# ADC.net
KiCad netlist of a schematic drawn in Altium Designer
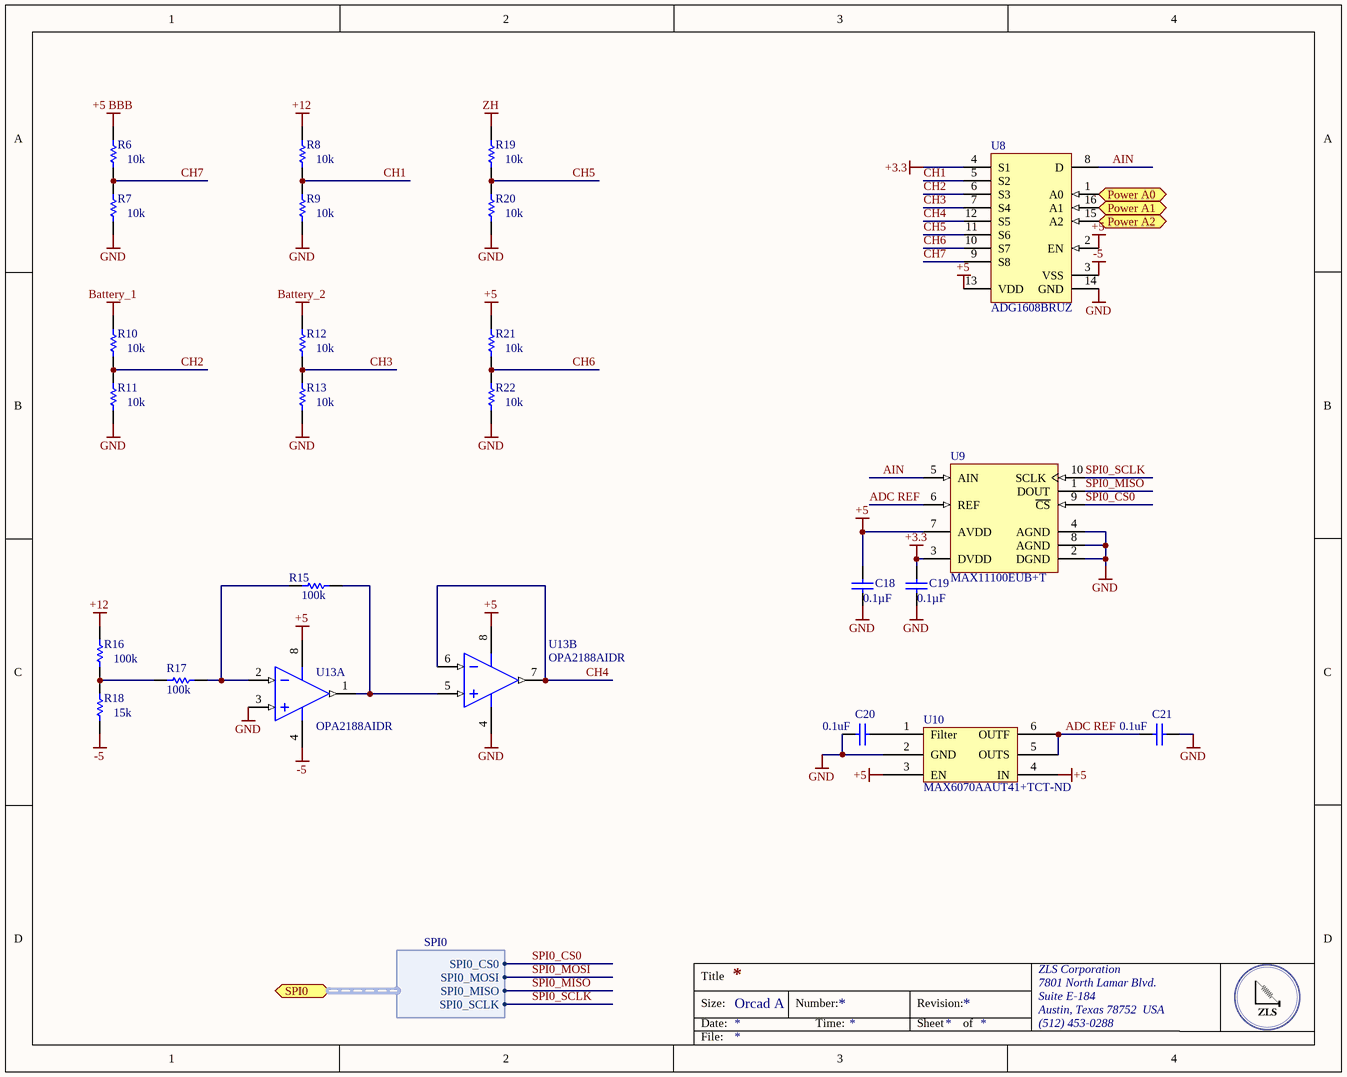
[diagram p0: ADC.SchDoc]

(export (version "E")
  (design (tool "Eeschema 10.0.6"))
  (components
    (comp (ref "C18")
      (value "CAP CER 0.1UF 25V X7R 0805")
      (footprint "CAPC0805(2012)145_N")
      (fields
        (field (name "MANUFACTURER") "Murata Electronics North America")
        (field (name "MANUFACTURER PART NUMBER") "GRM21BR71E104KA01L")
        (field (name "CAPACITANCE") "0.1µF")
        (field (name "TOLERANCE") "±10%")
      )
      (libsource (lib "Altium Content Vault") (part "CMP-1036-04795-1"))
    )
    (comp (ref "C19")
      (value "CAP CER 0.1UF 25V X7R 0805")
      (footprint "CAPC0805(2012)145_N")
      (fields
        (field (name "MANUFACTURER") "Murata Electronics North America")
        (field (name "MANUFACTURER PART NUMBER") "GRM21BR71E104KA01L")
        (field (name "CAPACITANCE") "0.1µF")
        (field (name "TOLERANCE") "±10%")
      )
      (libsource (lib "Altium Content Vault") (part "CMP-1036-04795-1"))
    )
    (comp (ref "C20")
      (value "0.1uF")
      (footprint "CAPC0402(1005)60_L")
      (description "CAP CER 0.1UF 10V X7R 0402")
      (fields
        (field (name "MANUFACTURER") "Murata Electronics North America")
        (field (name "MANUFACTURER PART NUMBER") "GRM155R71A104KA01D")
      )
      (libsource (lib "Altium Content Vault") (part "CMP-1034-00252-1"))
    )
    (comp (ref "C21")
      (value "0.1uF")
      (footprint "CAPC0402(1005)60_L")
      (description "CAP CER 0.1UF 10V X7R 0402")
      (fields
        (field (name "MANUFACTURER") "Murata Electronics North America")
        (field (name "MANUFACTURER PART NUMBER") "GRM155R71A104KA01D")
      )
      (libsource (lib "Altium Content Vault") (part "CMP-1034-00252-1"))
    )
    (comp (ref "R6")
      (value "10k")
      (footprint "RESC0402(1005)_L")
      (libsource (lib "Altium Content Vault") (part "CMP-1011-00927-1"))
    )
    (comp (ref "R7")
      (value "10k")
      (footprint "RESC0402(1005)_L")
      (libsource (lib "Altium Content Vault") (part "CMP-1011-00927-1"))
    )
    (comp (ref "R8")
      (value "10k")
      (footprint "RESC0402(1005)_L")
      (libsource (lib "Altium Content Vault") (part "CMP-1011-00927-1"))
    )
    (comp (ref "R9")
      (value "10k")
      (footprint "RESC0402(1005)_L")
      (libsource (lib "Altium Content Vault") (part "CMP-1011-00927-1"))
    )
    (comp (ref "R10")
      (value "10k")
      (footprint "RESC0402(1005)_L")
      (libsource (lib "Altium Content Vault") (part "CMP-1011-00927-1"))
    )
    (comp (ref "R11")
      (value "10k")
      (footprint "RESC0402(1005)_L")
      (libsource (lib "Altium Content Vault") (part "CMP-1011-00927-1"))
    )
    (comp (ref "R12")
      (value "10k")
      (footprint "RESC0402(1005)_L")
      (libsource (lib "Altium Content Vault") (part "CMP-1011-00927-1"))
    )
    (comp (ref "R13")
      (value "10k")
      (footprint "RESC0402(1005)_L")
      (libsource (lib "Altium Content Vault") (part "CMP-1011-00927-1"))
    )
    (comp (ref "R15")
      (value "100k")
      (footprint "RESC0402(1005)_L")
      (libsource (lib "Altium Content Vault") (part "CMP-1011-00927-1"))
    )
    (comp (ref "R16")
      (value "100k")
      (footprint "RESC0402(1005)_L")
      (libsource (lib "Altium Content Vault") (part "CMP-1011-00927-1"))
    )
    (comp (ref "R17")
      (value "100k")
      (footprint "RESC0402(1005)_L")
      (libsource (lib "Altium Content Vault") (part "CMP-1011-00927-1"))
    )
    (comp (ref "R18")
      (value "15k")
      (footprint "RESC0402(1005)_L")
      (libsource (lib "Altium Content Vault") (part "CMP-1011-00927-1"))
    )
    (comp (ref "R19")
      (value "10k")
      (footprint "RESC0402(1005)_L")
      (libsource (lib "Altium Content Vault") (part "CMP-1011-00927-1"))
    )
    (comp (ref "R20")
      (value "10k")
      (footprint "RESC0402(1005)_L")
      (libsource (lib "Altium Content Vault") (part "CMP-1011-00927-1"))
    )
    (comp (ref "R21")
      (value "10k")
      (footprint "RESC0402(1005)_L")
      (libsource (lib "Altium Content Vault") (part "CMP-1011-00927-1"))
    )
    (comp (ref "R22")
      (value "10k")
      (footprint "RESC0402(1005)_L")
      (libsource (lib "Altium Content Vault") (part "CMP-1011-00927-1"))
    )
    (comp (ref "U8")
      (value "ADG1608BRUZ")
      (footprint "ADI-RU-16_M")
      (description "4.5 Ohm Ron, 8-Channel +/-5 V,+12 V, +5 V and +3.3 V Multiplexer, 16-pin SOP (RU-16), Tube")
      (fields (field (name "MANUFACTURER") "Analog Devices"))
      (libsource (lib "Altium Content Vault") (part "ADI-ADG1608-RU-16"))
    )
    (comp (ref "U9")
      (value "MAX11100EUB+T")
      (footprint "U10+2_L")
      (description "16-Bit, +5V, 200ksps ADC with 10uA Shutdown, 10-Pin uMAX, -40°C to +85°C, Pb-Free, Tape and Reel")
      (libsource (lib "Altium Content Vault") (part "CON-ADC-MAX11100-IL10"))
    )
    (comp (ref "U10")
      (value "MAX6070AAUT41+T")
      (footprint "SOT95P280X445-6N")
      (description "IC VREF SERIES 4.096V SOT23")
      (fields
        (field (name "SUPPLIER PART NUMBER 1") "MAX6070AAUT41+TCT-ND")
        (field (name "MANUFACTURER") "Maxim Integrated")
        (field (name "TOLERANCE") "±0.04%")
      )
      (libsource (lib "ZLS_Schematic_lib") (part "MAX6070AAUT41+T"))
    )
    (comp (ref "U13")
      (value "OPA2188AIDR")
      (footprint "D0008A_L")
      (fields (field (name "MANUFACTURER") "Texas Instruments"))
      (libsource (lib "Altium Content Vault") (part "TI-OPA-8_2"))
    )
  )
  (nets
    (net (code "2") (name "+3.3") (class "Default")
      (node (ref "C19") (pin "1") (pinfunction "1_1") (pintype "passive"))
      (node (ref "U8") (pin "4") (pinfunction "S1_4") (pintype "passive"))
      (node (ref "U9") (pin "3") (pinfunction "DVDD_3") (pintype "power_in"))
    )
    (net (code "3") (name "+5") (class "Default")
      (node (ref "C18") (pin "1") (pinfunction "1_1") (pintype "passive"))
      (node (ref "R21") (pin "2") (pinfunction "2_2") (pintype "passive"))
      (node (ref "U10") (pin "3") (pinfunction "EN_3") (pintype "passive"))
      (node (ref "U10") (pin "4") (pinfunction "IN_4") (pintype "passive"))
      (node (ref "U13") (pin "8") (pinfunction "V+_8") (pintype "power_in"))
      (node (ref "U8") (pin "13") (pinfunction "VDD_13") (pintype "power_in"))
      (node (ref "U8") (pin "2") (pinfunction "EN_2") (pintype "input"))
      (node (ref "U9") (pin "7") (pinfunction "AVDD_7") (pintype "power_in"))
    )
    (net (code "4") (name "+5 BBB") (class "Default")
      (node (ref "R6") (pin "2") (pinfunction "2_2") (pintype "passive"))
    )
    (net (code "5") (name "+12") (class "Default")
      (node (ref "R16") (pin "2") (pinfunction "2_2") (pintype "passive"))
      (node (ref "R8") (pin "2") (pinfunction "2_2") (pintype "passive"))
    )
    (net (code "6") (name "-5") (class "Default")
      (node (ref "R18") (pin "1") (pinfunction "1_1") (pintype "passive"))
      (node (ref "U13") (pin "4") (pinfunction "V-_4") (pintype "power_in"))
      (node (ref "U8") (pin "3") (pinfunction "VSS_3") (pintype "power_in"))
    )
    (net (code "7") (name "/ADC REF") (class "Default")
      (node (ref "C21") (pin "2") (pinfunction "2_2") (pintype "passive"))
      (node (ref "U10") (pin "5") (pinfunction "OUTS_5") (pintype "passive"))
      (node (ref "U10") (pin "6") (pinfunction "OUTF_6") (pintype "passive"))
      (node (ref "U9") (pin "6") (pinfunction "REF_6") (pintype "input"))
    )
    (net (code "8") (name "/AIN") (class "Default")
      (node (ref "U8") (pin "8") (pinfunction "D_8") (pintype "passive"))
      (node (ref "U9") (pin "5") (pinfunction "AIN_5") (pintype "input"))
    )
    (net (code "9") (name "/CH1") (class "Default")
      (node (ref "R8") (pin "1") (pinfunction "1_1") (pintype "passive"))
      (node (ref "R9") (pin "2") (pinfunction "2_2") (pintype "passive"))
      (node (ref "U8") (pin "5") (pinfunction "S2_5") (pintype "passive"))
    )
    (net (code "10") (name "/CH2") (class "Default")
      (node (ref "R10") (pin "1") (pinfunction "1_1") (pintype "passive"))
      (node (ref "R11") (pin "2") (pinfunction "2_2") (pintype "passive"))
      (node (ref "U8") (pin "6") (pinfunction "S3_6") (pintype "passive"))
    )
    (net (code "11") (name "/CH3") (class "Default")
      (node (ref "R12") (pin "1") (pinfunction "1_1") (pintype "passive"))
      (node (ref "R13") (pin "2") (pinfunction "2_2") (pintype "passive"))
      (node (ref "U8") (pin "7") (pinfunction "S4_7") (pintype "passive"))
    )
    (net (code "12") (name "/CH4") (class "Default")
      (node (ref "U13") (pin "6") (pinfunction "IN_B-_6") (pintype "input"))
      (node (ref "U13") (pin "7") (pinfunction "OUT_B_7") (pintype "output"))
      (node (ref "U8") (pin "12") (pinfunction "S5_12") (pintype "passive"))
    )
    (net (code "13") (name "/CH5") (class "Default")
      (node (ref "R19") (pin "1") (pinfunction "1_1") (pintype "passive"))
      (node (ref "R20") (pin "2") (pinfunction "2_2") (pintype "passive"))
      (node (ref "U8") (pin "11") (pinfunction "S6_11") (pintype "passive"))
    )
    (net (code "14") (name "/CH6") (class "Default")
      (node (ref "R21") (pin "1") (pinfunction "1_1") (pintype "passive"))
      (node (ref "R22") (pin "2") (pinfunction "2_2") (pintype "passive"))
      (node (ref "U8") (pin "10") (pinfunction "S7_10") (pintype "passive"))
    )
    (net (code "15") (name "/CH7") (class "Default")
      (node (ref "R6") (pin "1") (pinfunction "1_1") (pintype "passive"))
      (node (ref "R7") (pin "2") (pinfunction "2_2") (pintype "passive"))
      (node (ref "U8") (pin "9") (pinfunction "S8_9") (pintype "passive"))
    )
    (net (code "16") (name "/Power A0") (class "Default")
      (node (ref "U8") (pin "1") (pinfunction "A0_1") (pintype "input"))
    )
    (net (code "17") (name "/Power A1") (class "Default")
      (node (ref "U8") (pin "16") (pinfunction "A1_16") (pintype "input"))
    )
    (net (code "18") (name "/Power A2") (class "Default")
      (node (ref "U8") (pin "15") (pinfunction "A2_15") (pintype "input"))
    )
    (net (code "19") (name "/SPI0_CS0") (class "Default")
      (node (ref "U9") (pin "9") (pinfunction "~{CS}_9") (pintype "input"))
    )
    (net (code "20") (name "/SPI0_MISO") (class "Default")
      (node (ref "U9") (pin "1") (pinfunction "DOUT_1") (pintype "tri_state"))
    )
    (net (code "22") (name "/SPI0_SCLK") (class "Default")
      (node (ref "U9") (pin "10") (pinfunction "SCLK_10") (pintype "input"))
    )
    (net (code "24") (name "Battery_1") (class "Default")
      (node (ref "R10") (pin "2") (pinfunction "2_2") (pintype "passive"))
    )
    (net (code "25") (name "Battery_2") (class "Default")
      (node (ref "R12") (pin "2") (pinfunction "2_2") (pintype "passive"))
    )
    (net (code "26") (name "GND") (class "Default")
      (node (ref "C18") (pin "2") (pinfunction "2_2") (pintype "passive"))
      (node (ref "C19") (pin "2") (pinfunction "2_2") (pintype "passive"))
      (node (ref "C20") (pin "2") (pinfunction "2_2") (pintype "passive"))
      (node (ref "C21") (pin "1") (pinfunction "1_1") (pintype "passive"))
      (node (ref "R11") (pin "1") (pinfunction "1_1") (pintype "passive"))
      (node (ref "R13") (pin "1") (pinfunction "1_1") (pintype "passive"))
      (node (ref "R20") (pin "1") (pinfunction "1_1") (pintype "passive"))
      (node (ref "R22") (pin "1") (pinfunction "1_1") (pintype "passive"))
      (node (ref "R7") (pin "1") (pinfunction "1_1") (pintype "passive"))
      (node (ref "R9") (pin "1") (pinfunction "1_1") (pintype "passive"))
      (node (ref "U10") (pin "2") (pinfunction "GND_2") (pintype "passive"))
      (node (ref "U13") (pin "3") (pinfunction "IN_A+_3") (pintype "input"))
      (node (ref "U13") (pin "4") (pinfunction "V-_4") (pintype "power_in"))
      (node (ref "U8") (pin "14") (pinfunction "GND_14") (pintype "power_in"))
      (node (ref "U9") (pin "2") (pinfunction "DGND_2") (pintype "power_in"))
      (node (ref "U9") (pin "4") (pinfunction "AGND_4") (pintype "power_in"))
      (node (ref "U9") (pin "8") (pinfunction "AGND_8") (pintype "power_in"))
    )
    (net (code "27") (name "Net-(R16-Pad1)") (class "Default")
      (node (ref "R16") (pin "1") (pinfunction "1_1") (pintype "passive"))
      (node (ref "R17") (pin "2") (pinfunction "2_2") (pintype "passive"))
      (node (ref "R18") (pin "2") (pinfunction "2_2") (pintype "passive"))
    )
    (net (code "28") (name "Net-(U10-Filter)") (class "Default")
      (node (ref "C20") (pin "1") (pinfunction "1_1") (pintype "passive"))
      (node (ref "U10") (pin "1") (pinfunction "Filter_1") (pintype "passive"))
    )
    (net (code "29") (name "Net-(U13A-IN_A-)") (class "Default")
      (node (ref "R15") (pin "2") (pinfunction "2_2") (pintype "passive"))
      (node (ref "R17") (pin "1") (pinfunction "1_1") (pintype "passive"))
      (node (ref "U13") (pin "2") (pinfunction "IN_A-_2") (pintype "input"))
    )
    (net (code "30") (name "Net-(U13A-OUT_A)") (class "Default")
      (node (ref "R15") (pin "1") (pinfunction "1_1") (pintype "passive"))
      (node (ref "U13") (pin "1") (pinfunction "OUT_A_1") (pintype "output"))
      (node (ref "U13") (pin "5") (pinfunction "IN_B+_5") (pintype "input"))
    )
    (net (code "31") (name "ZH") (class "Default")
      (node (ref "R19") (pin "2") (pinfunction "2_2") (pintype "passive"))
    )
  )
)
